# SAMD21.net
KiCad netlist of a schematic drawn in Altium Designer
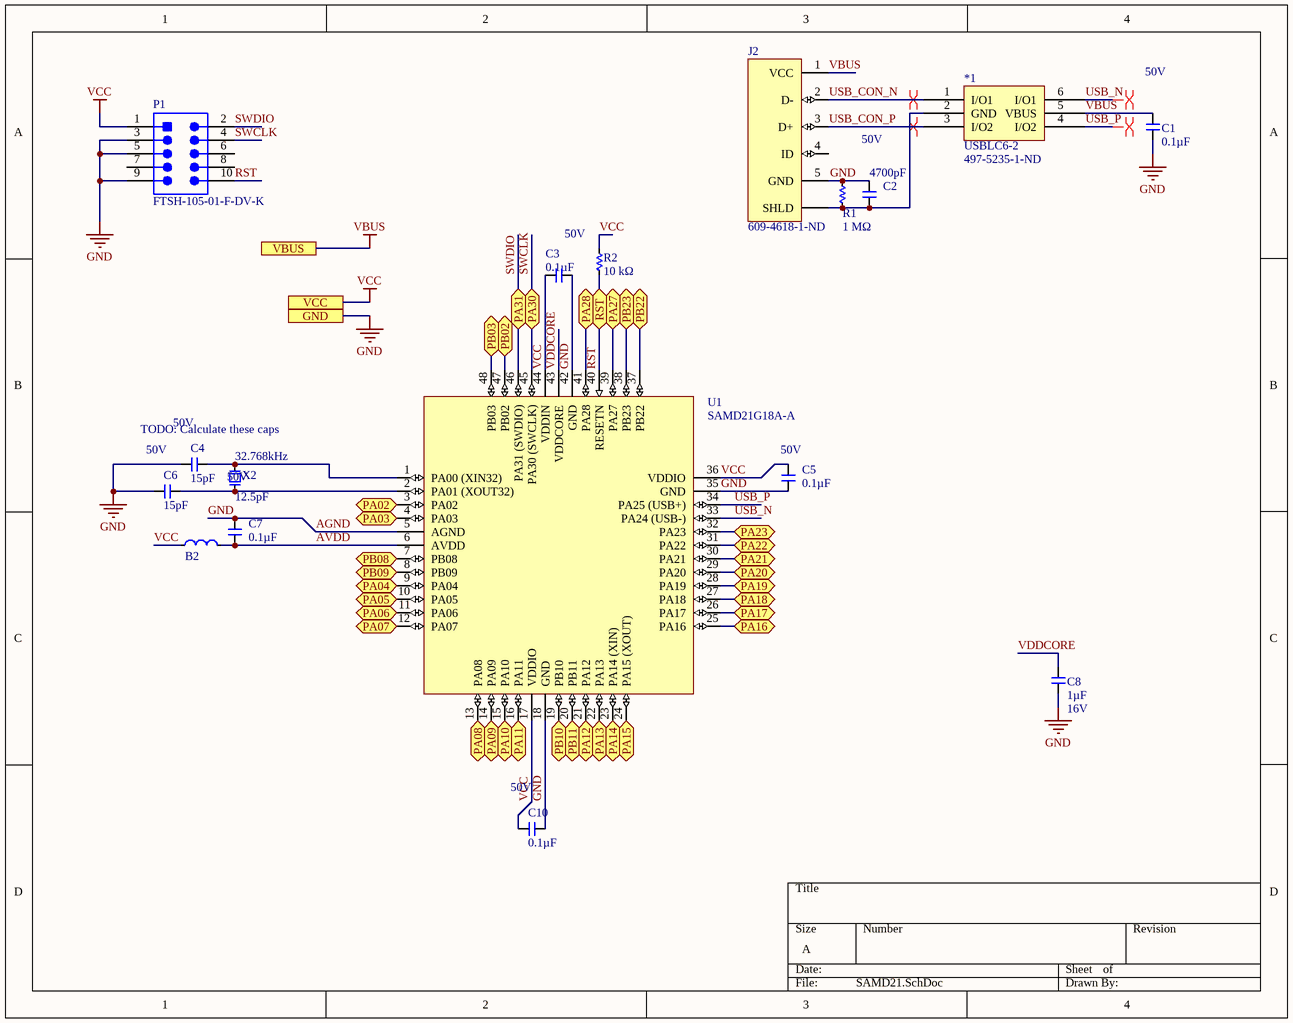
[diagram p0: SAMD21.SchDoc]

(export (version "E")
  (design (tool "Eeschema 10.0.6"))
  (components
    (comp (ref "*1")
      (value "USBLC6-2")
      (footprint "6SOT23")
      (fields
        (field (name "MANUFACTURER") "STMicroelectronics")
        (field (name "MANUFACTURER PART NUMBER") "USBLC6-2SC6")
        (field (name "SUPPLIER PART NUMBER 1") "497-5235-1-ND")
      )
      (libsource (lib "SSI") (part "USBLC6-2"))
    )
    (comp (ref "B2")
      (value "FB_1608")
      (footprint "R0603")
      (description "FERRITE BEAD 600 OHM 300mA")
      (fields
        (field (name "MANUFACTURER") "Taiyo Yuden")
        (field (name "MANUFACTURER PART NUMBER") "BK1608HW601-T")
      )
      (libsource (lib "SSI") (part "FB_1608"))
    )
    (comp (ref "C1")
      (value "__template_cap")
      (footprint "C0603")
      (description "CAP CER 0603 0.1µF X7R 50V 10%")
      (fields
        (field (name "CAPACITANCE (SHORTHAND)") "0.1µF")
        (field (name "MANUFACTURER") "Murata Electronics North America")
        (field (name "RATED VOLTAGE") "50V")
      )
      (libsource (lib "passives") (part "__template_cap"))
    )
    (comp (ref "C2")
      (value "__template_cap")
      (footprint "C0603")
      (description "CAP CER 0603 4700pF X7R 50V 10%")
      (fields
        (field (name "CAPACITANCE (SHORTHAND)") "4700pF")
        (field (name "MANUFACTURER") "Murata Electronics North America")
        (field (name "RATED VOLTAGE") "50V")
      )
      (libsource (lib "passives") (part "__template_cap"))
    )
    (comp (ref "C3")
      (value "__template_cap")
      (footprint "C0603")
      (description "CAP CER 0603 0.1µF X7R 50V 10%")
      (fields
        (field (name "CAPACITANCE (SHORTHAND)") "0.1µF")
        (field (name "MANUFACTURER") "Murata Electronics North America")
        (field (name "RATED VOLTAGE") "50V")
      )
      (libsource (lib "passives") (part "__template_cap"))
    )
    (comp (ref "C4")
      (value "__template_cap")
      (footprint "C0603")
      (description "CAP CER 15PF 50V C0G/NP0 0603")
      (fields
        (field (name "CAPACITANCE (SHORTHAND)") "15pF")
        (field (name "MANUFACTURER") "Murata Electronics North America")
        (field (name "RATED VOLTAGE") "50V")
      )
      (libsource (lib "passives") (part "__template_cap"))
    )
    (comp (ref "C5")
      (value "__template_cap")
      (footprint "C0603")
      (description "CAP CER 0603 0.1µF X7R 50V 10%")
      (fields
        (field (name "CAPACITANCE (SHORTHAND)") "0.1µF")
        (field (name "MANUFACTURER") "Murata Electronics North America")
        (field (name "RATED VOLTAGE") "50V")
      )
      (libsource (lib "passives") (part "__template_cap"))
    )
    (comp (ref "C6")
      (value "__template_cap")
      (footprint "C0603")
      (description "CAP CER 15PF 50V C0G/NP0 0603")
      (fields
        (field (name "CAPACITANCE (SHORTHAND)") "15pF")
        (field (name "MANUFACTURER") "Murata Electronics North America")
        (field (name "RATED VOLTAGE") "50V")
      )
      (libsource (lib "passives") (part "__template_cap"))
    )
    (comp (ref "C7")
      (value "__template_cap")
      (footprint "C0603")
      (description "CAP CER 0603 0.1µF X7R 50V 10%")
      (fields
        (field (name "CAPACITANCE (SHORTHAND)") "0.1µF")
        (field (name "MANUFACTURER") "Murata Electronics North America")
        (field (name "RATED VOLTAGE") "50V")
      )
      (libsource (lib "passives") (part "__template_cap"))
    )
    (comp (ref "C8")
      (value "__template_cap")
      (footprint "C0603")
      (description "CAP CER 0603 1µF X7R 16V 10%")
      (fields
        (field (name "CAPACITANCE (SHORTHAND)") "1µF")
        (field (name "RATED VOLTAGE") "16V")
        (field (name "MANUFACTURER") "Murata Electronics North America")
      )
      (libsource (lib "passives") (part "__template_cap"))
    )
    (comp (ref "C10")
      (value "__template_cap")
      (footprint "C0603")
      (description "CAP CER 0603 0.1µF X7R 50V 10%")
      (fields
        (field (name "CAPACITANCE (SHORTHAND)") "0.1µF")
        (field (name "MANUFACTURER") "Murata Electronics North America")
        (field (name "RATED VOLTAGE") "50V")
      )
      (libsource (lib "passives") (part "__template_cap"))
    )
    (comp (ref "J2")
      (value "CONN_USB_MICROB_SMD_TH_R/A")
      (footprint "CONN_USBMICROB_10118194-0001LF")
      (description "CONN RCPT USB2.0 MICRO B SMD R/A")
      (fields
        (field (name "MANUFACTURER") "Amphenol FCI")
        (field (name "MANUFACTURER PART NUMBER") "10118194-0001LF")
        (field (name "SUPPLIER PART NUMBER 1") "609-4618-1-ND")
      )
      (libsource (lib "SSI") (part "CONN_USB_MICROB_SMD_TH_R/A"))
    )
    (comp (ref "P1")
      (value "FTSH-105-01-F-DV-K")
      (footprint "SMTC-FTSH-105-01-L-DV-K_V")
      (description "Male Header, Pitch 1.27 mm, 2 x 5 Position, Height 6.12 mm, RoHS, Tube")
      (fields (field (name "MANUFACTURER") "Samtec"))
      (libsource (lib "Altium Content Vault") (part "CN-2P-M-R10"))
    )
    (comp (ref "R1")
      (value "__template_resistor")
      (footprint "R0603")
      (description "RES SMD 1M OHM 1% 1/10W 0603")
      (fields
        (field (name "RESISTANCE") "1 MΩ")
        (field (name "MANUFACTURER PART NUMBER") "RC0603FR-071ML")
        (field (name "MANUFACTURER") "Yageo")
      )
      (libsource (lib "passives") (part "__template_resistor"))
    )
    (comp (ref "R2")
      (value "__template_resistor")
      (footprint "R0603")
      (description "RES SMD 10K OHM 1% 1/10W 0603")
      (fields
        (field (name "RESISTANCE") "10 kΩ")
        (field (name "MANUFACTURER PART NUMBER") "RC0603FR-0710KL")
        (field (name "MANUFACTURER") "Yageo")
      )
      (libsource (lib "passives") (part "__template_resistor"))
    )
    (comp (ref "U1")
      (value "SAMD21G18A-A")
      (footprint "SAMD21 TQFP-48")
      (description "48Mhz Atmel SAM ARM Cortex M0+")
      (libsource (lib "SSI") (part "SAMD21G18A-A"))
    )
    (comp (ref "X2")
      (value "XTAL_9HT10-32.768KEZF-T")
      (footprint "XTAL_TXC_9HT10")
      (description "CRYSTAL 32.768 KHZ 12.5 PF SMD")
      (fields
        (field (name "MANUFACTURER") "TXC CORPORATION")
        (field (name "MANUFACTURER PART NUMBER") "9HT10-32.768KEZF-T")
        (field (name "FREQUENCY") "32.768kHz")
        (field (name "LOAD CAPACITANCE") "12.5pF")
      )
      (libsource (lib "SSI") (part "XTAL_9HT10-32.768KEZF-T"))
    )
  )
  (nets
    (net (code "1") (name "/AVDD") (class "Default")
      (node (ref "B2") (pin "2") (pinfunction "2_2") (pintype "passive"))
      (node (ref "C7") (pin "2") (pintype "passive"))
      (node (ref "U1") (pin "6") (pinfunction "AVDD_6") (pintype "power_in"))
    )
    (net (code "2") (name "/PA02") (class "Default")
      (node (ref "U1") (pin "3") (pinfunction "PA02_3") (pintype "bidirectional"))
    )
    (net (code "3") (name "/PA03") (class "Default")
      (node (ref "U1") (pin "4") (pinfunction "PA03_4") (pintype "bidirectional"))
    )
    (net (code "4") (name "/PA04") (class "Default")
      (node (ref "U1") (pin "9") (pinfunction "PA04_9") (pintype "bidirectional"))
    )
    (net (code "5") (name "/PA05") (class "Default")
      (node (ref "U1") (pin "10") (pinfunction "PA05_10") (pintype "bidirectional"))
    )
    (net (code "6") (name "/PA06") (class "Default")
      (node (ref "U1") (pin "11") (pinfunction "PA06_11") (pintype "bidirectional"))
    )
    (net (code "7") (name "/PA07") (class "Default")
      (node (ref "U1") (pin "12") (pinfunction "PA07_12") (pintype "bidirectional"))
    )
    (net (code "8") (name "/PA08") (class "Default")
      (node (ref "U1") (pin "13") (pinfunction "PA08_13") (pintype "bidirectional"))
    )
    (net (code "9") (name "/PA09") (class "Default")
      (node (ref "U1") (pin "14") (pinfunction "PA09_14") (pintype "bidirectional"))
    )
    (net (code "10") (name "/PA10") (class "Default")
      (node (ref "U1") (pin "15") (pinfunction "PA10_15") (pintype "bidirectional"))
    )
    (net (code "11") (name "/PA11") (class "Default")
      (node (ref "U1") (pin "16") (pinfunction "PA11_16") (pintype "bidirectional"))
    )
    (net (code "12") (name "/PA12") (class "Default")
      (node (ref "U1") (pin "21") (pinfunction "PA12_21") (pintype "bidirectional"))
    )
    (net (code "13") (name "/PA13") (class "Default")
      (node (ref "U1") (pin "22") (pinfunction "PA13_22") (pintype "bidirectional"))
    )
    (net (code "14") (name "/PA14") (class "Default")
      (node (ref "U1") (pin "23") (pinfunction "PA14_(XIN)_23") (pintype "bidirectional"))
    )
    (net (code "15") (name "/PA15") (class "Default")
      (node (ref "U1") (pin "24") (pinfunction "PA15_(XOUT)_24") (pintype "bidirectional"))
    )
    (net (code "16") (name "/PA16") (class "Default")
      (node (ref "U1") (pin "25") (pinfunction "PA16_25") (pintype "bidirectional"))
    )
    (net (code "17") (name "/PA17") (class "Default")
      (node (ref "U1") (pin "26") (pinfunction "PA17_26") (pintype "bidirectional"))
    )
    (net (code "18") (name "/PA18") (class "Default")
      (node (ref "U1") (pin "27") (pinfunction "PA18_27") (pintype "bidirectional"))
    )
    (net (code "19") (name "/PA19") (class "Default")
      (node (ref "U1") (pin "28") (pinfunction "PA19_28") (pintype "bidirectional"))
    )
    (net (code "20") (name "/PA20") (class "Default")
      (node (ref "U1") (pin "29") (pinfunction "PA20_29") (pintype "bidirectional"))
    )
    (net (code "21") (name "/PA21") (class "Default")
      (node (ref "U1") (pin "30") (pinfunction "PA21_30") (pintype "bidirectional"))
    )
    (net (code "22") (name "/PA22") (class "Default")
      (node (ref "U1") (pin "31") (pinfunction "PA22_31") (pintype "bidirectional"))
    )
    (net (code "23") (name "/PA23") (class "Default")
      (node (ref "U1") (pin "32") (pinfunction "PA23_32") (pintype "bidirectional"))
    )
    (net (code "24") (name "/PA27") (class "Default")
      (node (ref "U1") (pin "39") (pinfunction "PA27_39") (pintype "bidirectional"))
    )
    (net (code "25") (name "/PA28") (class "Default")
      (node (ref "U1") (pin "41") (pinfunction "PA28_41") (pintype "bidirectional"))
    )
    (net (code "26") (name "/PB02") (class "Default")
      (node (ref "U1") (pin "47") (pinfunction "PB02_47") (pintype "bidirectional"))
    )
    (net (code "27") (name "/PB03") (class "Default")
      (node (ref "U1") (pin "48") (pinfunction "PB03_48") (pintype "bidirectional"))
    )
    (net (code "28") (name "/PB08") (class "Default")
      (node (ref "U1") (pin "7") (pinfunction "PB08_7") (pintype "bidirectional"))
    )
    (net (code "29") (name "/PB09") (class "Default")
      (node (ref "U1") (pin "8") (pinfunction "PB09_8") (pintype "bidirectional"))
    )
    (net (code "30") (name "/PB10") (class "Default")
      (node (ref "U1") (pin "19") (pinfunction "PB10_19") (pintype "bidirectional"))
    )
    (net (code "31") (name "/PB11") (class "Default")
      (node (ref "U1") (pin "20") (pinfunction "PB11_20") (pintype "bidirectional"))
    )
    (net (code "32") (name "/PB22") (class "Default")
      (node (ref "U1") (pin "37") (pinfunction "PB22_37") (pintype "bidirectional"))
    )
    (net (code "33") (name "/PB23") (class "Default")
      (node (ref "U1") (pin "38") (pinfunction "PB23_38") (pintype "bidirectional"))
    )
    (net (code "34") (name "/RST") (class "Default")
      (node (ref "P1") (pin "10") (pinfunction "10_10") (pintype "passive"))
      (node (ref "R2") (pin "1") (pintype "passive"))
      (node (ref "U1") (pin "40") (pinfunction "RESETN_40") (pintype "input"))
    )
    (net (code "35") (name "/SWCLK") (class "Default")
      (node (ref "P1") (pin "4") (pinfunction "4_4") (pintype "passive"))
      (node (ref "U1") (pin "45") (pinfunction "PA30_(SWCLK)_45") (pintype "bidirectional"))
    )
    (net (code "36") (name "/SWDIO") (class "Default")
      (node (ref "P1") (pin "2") (pinfunction "2_2") (pintype "passive"))
      (node (ref "U1") (pin "46") (pinfunction "PA31_(SWDIO)_46") (pintype "bidirectional"))
    )
    (net (code "37") (name "/USB_CON_N") (class "Default")
      (node (ref "*1") (pin "1") (pinfunction "I/O1_1") (pintype "passive"))
      (node (ref "J2") (pin "2") (pinfunction "D-_2") (pintype "bidirectional"))
    )
    (net (code "38") (name "/USB_CON_P") (class "Default")
      (node (ref "*1") (pin "3") (pinfunction "I/O2_3") (pintype "passive"))
      (node (ref "J2") (pin "3") (pinfunction "D+_3") (pintype "bidirectional"))
    )
    (net (code "39") (name "/USB_N") (class "Default")
      (node (ref "*1") (pin "6") (pinfunction "I/O1_6") (pintype "passive"))
      (node (ref "U1") (pin "33") (pinfunction "PA24_(USB-)_33") (pintype "bidirectional"))
    )
    (net (code "40") (name "/USB_P") (class "Default")
      (node (ref "*1") (pin "4") (pinfunction "I/O2_4") (pintype "passive"))
      (node (ref "U1") (pin "34") (pinfunction "PA25_(USB+)_34") (pintype "bidirectional"))
    )
    (net (code "41") (name "/VDDCORE") (class "Default")
      (node (ref "C8") (pin "1") (pintype "passive"))
      (node (ref "U1") (pin "43") (pinfunction "VDDCORE_43") (pintype "power_in"))
    )
    (net (code "42") (name "GND") (class "Default")
      (node (ref "C1") (pin "2") (pintype "passive"))
      (node (ref "C10") (pin "2") (pintype "passive"))
      (node (ref "C2") (pin "1") (pintype "passive"))
      (node (ref "C3") (pin "1") (pintype "passive"))
      (node (ref "C4") (pin "1") (pintype "passive"))
      (node (ref "C5") (pin "1") (pintype "passive"))
      (node (ref "C6") (pin "1") (pintype "passive"))
      (node (ref "C7") (pin "1") (pintype "passive"))
      (node (ref "C8") (pin "2") (pintype "passive"))
      (node (ref "J2") (pin "5") (pinfunction "GND_5") (pintype "power_in"))
      (node (ref "P1") (pin "3") (pinfunction "3_3") (pintype "passive"))
      (node (ref "P1") (pin "5") (pinfunction "5_5") (pintype "passive"))
      (node (ref "P1") (pin "9") (pinfunction "9_9") (pintype "passive"))
      (node (ref "R1") (pin "2") (pintype "passive"))
      (node (ref "U1") (pin "18") (pinfunction "GND_18") (pintype "power_in"))
      (node (ref "U1") (pin "35") (pinfunction "GND_35") (pintype "power_in"))
      (node (ref "U1") (pin "42") (pinfunction "GND_42") (pintype "power_in"))
      (node (ref "U1") (pin "5") (pinfunction "AGND_5") (pintype "power_in"))
    )
    (net (code "43") (name "Net-(*1-GND)") (class "Default")
      (node (ref "*1") (pin "2") (pinfunction "GND_2") (pintype "passive"))
      (node (ref "C2") (pin "2") (pintype "passive"))
      (node (ref "J2") (pin "SHIELD") (pinfunction "SHLD_SHIELD") (pintype "power_in"))
      (node (ref "R1") (pin "1") (pintype "passive"))
    )
    (net (code "44") (name "Net-(U1-PA00_(XIN32))") (class "Default")
      (node (ref "C4") (pin "2") (pintype "passive"))
      (node (ref "U1") (pin "1") (pinfunction "PA00_(XIN32)_1") (pintype "bidirectional"))
      (node (ref "X2") (pin "2") (pinfunction "2_2") (pintype "passive"))
    )
    (net (code "45") (name "Net-(U1-PA01_(XOUT32))") (class "Default")
      (node (ref "C6") (pin "2") (pintype "passive"))
      (node (ref "U1") (pin "2") (pinfunction "PA01_(XOUT32)_2") (pintype "bidirectional"))
      (node (ref "X2") (pin "1") (pinfunction "1_1") (pintype "passive"))
    )
    (net (code "46") (name "VBUS") (class "Default")
      (node (ref "*1") (pin "5") (pinfunction "VBUS_5") (pintype "passive"))
      (node (ref "C1") (pin "1") (pintype "passive"))
      (node (ref "J2") (pin "1") (pinfunction "VCC_1") (pintype "power_in"))
    )
    (net (code "47") (name "VCC") (class "Default")
      (node (ref "B2") (pin "1") (pinfunction "1_1") (pintype "passive"))
      (node (ref "C10") (pin "1") (pintype "passive"))
      (node (ref "C3") (pin "2") (pintype "passive"))
      (node (ref "C5") (pin "2") (pintype "passive"))
      (node (ref "P1") (pin "1") (pinfunction "1_1") (pintype "passive"))
      (node (ref "R2") (pin "2") (pintype "passive"))
      (node (ref "U1") (pin "17") (pinfunction "VDDIO_17") (pintype "power_in"))
      (node (ref "U1") (pin "36") (pinfunction "VDDIO_36") (pintype "power_in"))
      (node (ref "U1") (pin "44") (pinfunction "VDDIN_44") (pintype "power_in"))
    )
    (net (code "48") (name "unconnected-(J2-ID-Pad4)") (class "Default")
      (node (ref "J2") (pin "4") (pinfunction "ID_4") (pintype "bidirectional"))
    )
    (net (code "49") (name "unconnected-(P1-Pad6)") (class "Default")
      (node (ref "P1") (pin "6") (pinfunction "6_6") (pintype "passive"))
    )
    (net (code "50") (name "unconnected-(P1-Pad7)") (class "Default")
      (node (ref "P1") (pin "7") (pinfunction "7_7") (pintype "passive"))
    )
    (net (code "51") (name "unconnected-(P1-Pad8)") (class "Default")
      (node (ref "P1") (pin "8") (pinfunction "8_8") (pintype "passive"))
    )
  )
)
